# Buck_Converter.net
KiCad netlist of a schematic drawn in Altium Designer
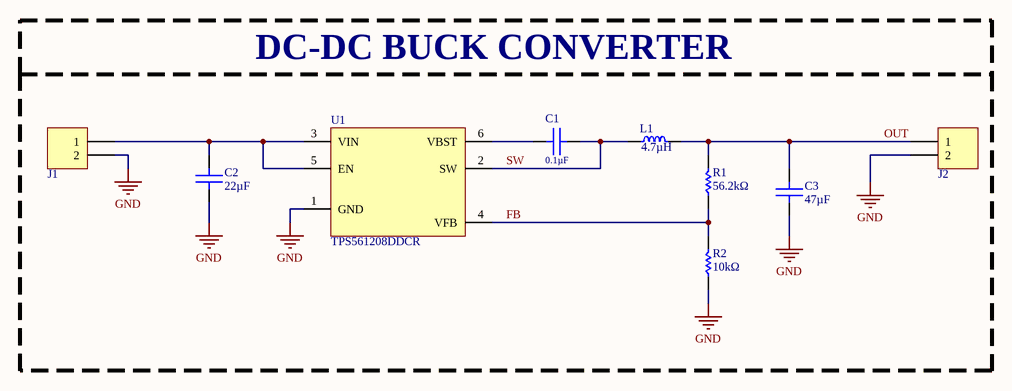
[diagram p0: Buck Converter.SchDoc]

(export (version "E")
  (design (tool "Eeschema 10.0.6"))
  (components
    (comp (ref "C1")
      (value "0.1µF")
      (footprint "CAP_ALUM_0603")
      (description "CAP CER 0.1UF 50V X7R 0603")
      (fields (field (name "Comment") "CC0603KRX7R9BB104") (field (name "DESIGNED BY") "Ali"))
      (libsource (lib "Buck Converter") (part "CAP CER 50V 0.1UF"))
    )
    (comp (ref "C2")
      (value "22µF")
      (footprint "CAP_ALUM_0603")
      (description "CAP CER 22UF 16V X5R 0603")
      (fields (field (name "Comment") "GMC10X5R226M16NT") (field (name "DESIGNED BY") "Ali"))
      (libsource (lib "Buck Converter") (part "CAP CER 16V 22UF"))
    )
    (comp (ref "C3")
      (value "47µF")
      (footprint "CAP_ALUM_0805")
      (description "CAP CER 47UF 10V X5R 0805")
      (fields (field (name "Comment") "MLASL21GBB5476MTNA01") (field (name "DESIGNED BY") "Ali"))
      (libsource (lib "Buck Converter") (part "CAP CER 10V 47UF"))
    )
    (comp (ref "J1")
      (value "284391-2")
      (footprint "CONNECTOR")
      (description "TERM BLK 2POS 3.5MM PCB")
      (fields (field (name "DESIGNED BY") "Ali"))
      (libsource (lib "") (part "2POS CONNECTOR_1"))
    )
    (comp (ref "J2")
      (value "284391-2")
      (footprint "CONNECTOR")
      (description "TERM BLK 2POS 3.5MM PCB")
      (fields (field (name "DESIGNED BY") "Ali"))
      (libsource (lib "Buck Converter") (part "2POS CONNECTOR"))
    )
    (comp (ref "L1")
      (value "4.7µH")
      (footprint "IND")
      (description "FIXED IND 4.7UH 4.1A 50.16 MOHM")
      (fields
        (field (name "MANUFACTURER") "Panasonic")
        (field (name "MANUFACTURER PART NUMBER") "ETQP3M4R7KVP")
        (field (name "DESIGNED BY") "Ali")
      )
      (libsource (lib "Buck Converter") (part "IND SMD 4.7UH 4.1A"))
    )
    (comp (ref "R1")
      (value "56.2kΩ")
      (footprint "RES_0805")
      (description "RES SMD 56.2K OHM 0.5% 1/4W 0805")
      (fields (field (name "Comment") "ERJ-PB6D5622V") (field (name "DESIGNED BY") "Ali"))
      (libsource (lib "Buck Converter") (part "RES SMD 56.2K OHM 0805"))
    )
    (comp (ref "R2")
      (value "10kΩ")
      (footprint "RES_0805")
      (description "RES SMD 10K OHM 1% 1/4W 0805")
      (fields (field (name "Comment") "CRCW080510K0FKEA") (field (name "DESIGNED BY") "Ali"))
      (libsource (lib "Buck Converter") (part "RES SMD 10K OHM 0805"))
    )
    (comp (ref "U1")
      (value "TPS561208DDCR")
      (footprint "SOT-23-6")
      (description "IC REG BUCK ADJ 1A SOT23")
      (fields (field (name "DESIGNED BY") "Ali"))
      (libsource (lib "Buck Converter") (part "BUCK SWITCHING 5V 1A"))
    )
  )
  (nets
    (net (code "1") (name "/FB") (class "Default")
      (node (ref "R1") (pin "1") (pinfunction "1_1") (pintype "passive"))
      (node (ref "R2") (pin "2") (pinfunction "2_2") (pintype "passive"))
      (node (ref "U1") (pin "4") (pinfunction "VFB_4") (pintype "passive"))
    )
    (net (code "2") (name "/OUT") (class "Default")
      (node (ref "C3") (pin "2") (pinfunction "2_2") (pintype "passive"))
      (node (ref "J2") (pin "1") (pinfunction "1_1") (pintype "passive"))
      (node (ref "L1") (pin "2") (pinfunction "2_2") (pintype "passive"))
      (node (ref "R1") (pin "2") (pinfunction "2_2") (pintype "passive"))
    )
    (net (code "3") (name "/SW") (class "Default")
      (node (ref "C1") (pin "2") (pinfunction "2_2") (pintype "passive"))
      (node (ref "L1") (pin "1") (pinfunction "1_1") (pintype "passive"))
      (node (ref "U1") (pin "2") (pinfunction "SW_2") (pintype "passive"))
    )
    (net (code "4") (name "GND") (class "Default")
      (node (ref "C2") (pin "1") (pinfunction "1_1") (pintype "passive"))
      (node (ref "C3") (pin "1") (pinfunction "1_1") (pintype "passive"))
      (node (ref "J1") (pin "2") (pinfunction "2_2") (pintype "passive"))
      (node (ref "J2") (pin "2") (pinfunction "2_2") (pintype "passive"))
      (node (ref "R2") (pin "1") (pinfunction "1_1") (pintype "passive"))
      (node (ref "U1") (pin "1") (pinfunction "GND_1") (pintype "passive"))
    )
    (net (code "5") (name "Net-(U1-EN)") (class "Default")
      (node (ref "C2") (pin "2") (pinfunction "2_2") (pintype "passive"))
      (node (ref "J1") (pin "1") (pinfunction "1_1") (pintype "passive"))
      (node (ref "U1") (pin "3") (pinfunction "VIN_3") (pintype "passive"))
      (node (ref "U1") (pin "5") (pinfunction "EN_5") (pintype "passive"))
    )
    (net (code "6") (name "Net-(U1-VBST)") (class "Default")
      (node (ref "C1") (pin "1") (pinfunction "1_1") (pintype "passive"))
      (node (ref "U1") (pin "6") (pinfunction "VBST_6") (pintype "passive"))
    )
  )
)
